# logic.net
KiCad netlist of a schematic drawn in EAGLE
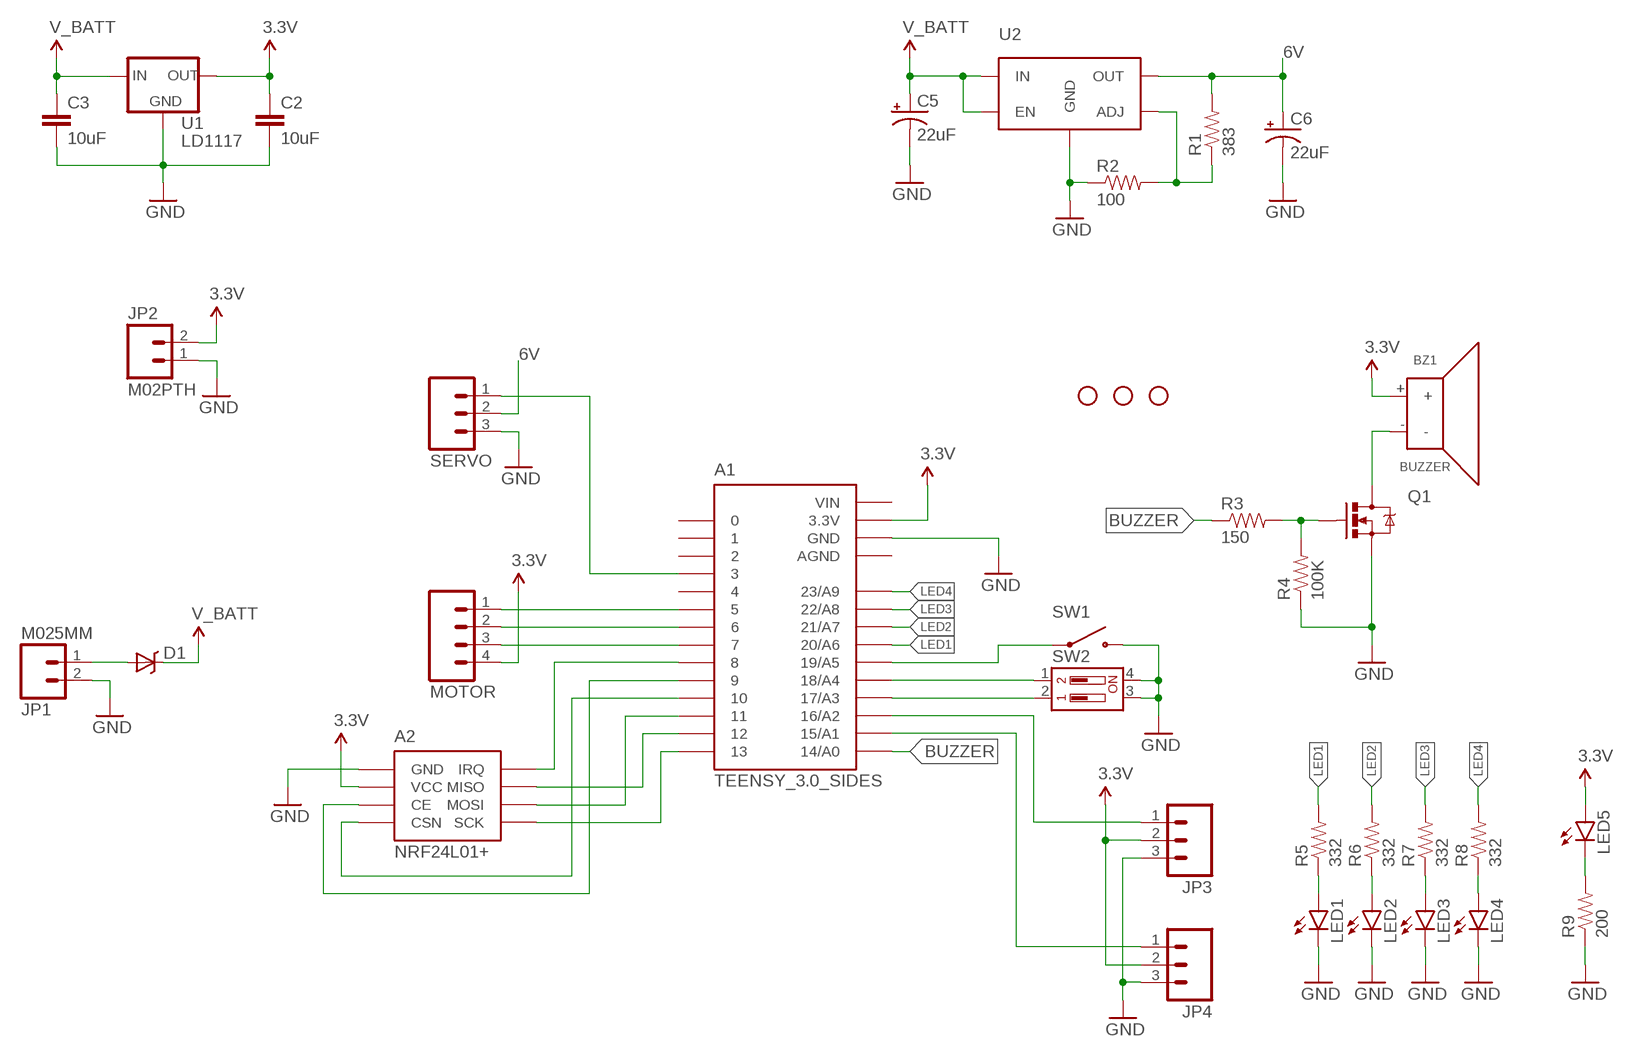
[diagram p0: schematic, sheet 1]

(export (version "E")
  (design (tool "Eeschema 10.0.6"))
  (components
    (comp (ref "A1")
      (value "TEENSY_3.0_SIDES")
      (footprint "eagle-import:TEENSY_3.0_SIDES")
      (libsource (lib "eagle-import") (part "TEENSY_3.0_SIDES"))
    )
    (comp (ref "A2")
      (value "NRF24L01+")
      (footprint "eagle-import:NRF24L01+")
      (libsource (lib "eagle-import") (part "NRF24L01+"))
    )
    (comp (ref "BZ1")
      (value "BUZZER")
      (footprint "eagle-import:BUZZER")
      (libsource (lib "eagle-import") (part "BUZZER"))
    )
    (comp (ref "C2")
      (value "10uF")
      (footprint "eagle-import:1206")
      (libsource (lib "eagle-import") (part "CAP1206"))
    )
    (comp (ref "C3")
      (value "10uF")
      (footprint "eagle-import:1206")
      (libsource (lib "eagle-import") (part "CAP1206"))
    )
    (comp (ref "C5")
      (value "22uF")
      (footprint "eagle-import:CPOL-RADIAL-10UF-25V")
      (libsource (lib "eagle-import") (part "CAP_POLPTH2"))
    )
    (comp (ref "C6")
      (value "22uF")
      (footprint "eagle-import:CPOL-RADIAL-10UF-25V")
      (libsource (lib "eagle-import") (part "CAP_POLPTH2"))
    )
    (comp (ref "D1")
      (value "DIODE-SCHOTTKY_")
      (footprint "eagle-import:SMA-DIODE")
      (libsource (lib "eagle-import") (part "DIODE-SCHOTTKY_"))
    )
    (comp (ref "JP1")
      (value "M025MM")
      (footprint "eagle-import:SCREWTERMINAL-5MM-2")
      (libsource (lib "eagle-import") (part "M025MM"))
    )
    (comp (ref "JP2")
      (value "M02PTH")
      (footprint "eagle-import:1X02")
      (libsource (lib "eagle-import") (part "M02PTH"))
    )
    (comp (ref "JP3")
      (value "M03LOCK")
      (footprint "eagle-import:1X03_LOCK")
      (libsource (lib "eagle-import") (part "M03LOCK"))
    )
    (comp (ref "JP4")
      (value "M03LOCK")
      (footprint "eagle-import:1X03_LOCK")
      (libsource (lib "eagle-import") (part "M03LOCK"))
    )
    (comp (ref "LED1")
      (value "LED0603")
      (footprint "eagle-import:LED-0603")
      (libsource (lib "eagle-import") (part "LED0603"))
    )
    (comp (ref "LED2")
      (value "LED0603")
      (footprint "eagle-import:LED-0603")
      (libsource (lib "eagle-import") (part "LED0603"))
    )
    (comp (ref "LED3")
      (value "LED0603")
      (footprint "eagle-import:LED-0603")
      (libsource (lib "eagle-import") (part "LED0603"))
    )
    (comp (ref "LED4")
      (value "LED0603")
      (footprint "eagle-import:LED-0603")
      (libsource (lib "eagle-import") (part "LED0603"))
    )
    (comp (ref "LED5")
      (value "LED0603")
      (footprint "eagle-import:LED-0603")
      (libsource (lib "eagle-import") (part "LED0603"))
    )
    (comp (ref "MOTOR")
      (value "M04LOCK")
      (footprint "eagle-import:1X04_LOCK")
      (libsource (lib "eagle-import") (part "M04LOCK"))
    )
    (comp (ref "Q1")
      (value "MOSFET-NCHANNELBSS123LT1G")
      (footprint "eagle-import:SOT23-3")
      (libsource (lib "eagle-import") (part "MOSFET-NCHANNELBSS123LT1G"))
    )
    (comp (ref "R1")
      (value "383")
      (footprint "eagle-import:0603-RES")
      (libsource (lib "eagle-import") (part "RESISTOR0603-RES"))
    )
    (comp (ref "R2")
      (value "100")
      (footprint "eagle-import:0603-RES")
      (libsource (lib "eagle-import") (part "RESISTOR0603-RES"))
    )
    (comp (ref "R3")
      (value "150")
      (footprint "eagle-import:0603-RES")
      (libsource (lib "eagle-import") (part "RESISTOR0603-RES"))
    )
    (comp (ref "R4")
      (value "100K")
      (footprint "eagle-import:0603-RES")
      (libsource (lib "eagle-import") (part "RESISTOR0603-RES"))
    )
    (comp (ref "R5")
      (value "332")
      (footprint "eagle-import:0603-RES")
      (libsource (lib "eagle-import") (part "RESISTOR0603-RES"))
    )
    (comp (ref "R6")
      (value "332")
      (footprint "eagle-import:0603-RES")
      (libsource (lib "eagle-import") (part "RESISTOR0603-RES"))
    )
    (comp (ref "R7")
      (value "332")
      (footprint "eagle-import:0603-RES")
      (libsource (lib "eagle-import") (part "RESISTOR0603-RES"))
    )
    (comp (ref "R8")
      (value "332")
      (footprint "eagle-import:0603-RES")
      (libsource (lib "eagle-import") (part "RESISTOR0603-RES"))
    )
    (comp (ref "R9")
      (value "200")
      (footprint "eagle-import:0603-RES")
      (libsource (lib "eagle-import") (part "RESISTOR0603-RES"))
    )
    (comp (ref "SERVO")
      (value "M03LOCK_LONGPADS")
      (footprint "eagle-import:1X03_LOCK_LONGPADS")
      (libsource (lib "eagle-import") (part "M03LOCK_LONGPADS"))
    )
    (comp (ref "STANDOFF1")
      (value "STAND-OFF")
      (footprint "eagle-import:STAND-OFF")
      (libsource (lib "eagle-import") (part "STAND-OFF"))
    )
    (comp (ref "STANDOFF2")
      (value "STAND-OFF")
      (footprint "eagle-import:STAND-OFF")
      (libsource (lib "eagle-import") (part "STAND-OFF"))
    )
    (comp (ref "STANDOFF3")
      (value "STAND-OFF")
      (footprint "eagle-import:STAND-OFF")
      (libsource (lib "eagle-import") (part "STAND-OFF"))
    )
    (comp (ref "SW1")
      (value "FSM4JSMA")
      (footprint "eagle-import:FSM4JSMA")
      (libsource (lib "eagle-import") (part "FSM4JSMA"))
    )
    (comp (ref "SW2")
      (value "2-POS-DIPCTS-THRU-HOLE")
      (footprint "eagle-import:209-2LPST")
      (libsource (lib "eagle-import") (part "2-POS-DIPCTS-THRU-HOLE"))
    )
    (comp (ref "U1")
      (value "LD1117")
      (footprint "eagle-import:SOT-223")
      (libsource (lib "eagle-import") (part "LD1117"))
    )
    (comp (ref "U2")
      (value "MIC29302AWD")
      (footprint "eagle-import:TO-252-5")
      (libsource (lib "eagle-import") (part "MIC29302AWD"))
    )
  )
  (nets
    (net (code "1") (name "/6V") (class "Default")
      (node (ref "C6") (pin "1") (pinfunction "+_1") (pintype "passive"))
      (node (ref "R1") (pin "2") (pinfunction "2_2") (pintype "passive"))
      (node (ref "SERVO") (pin "2") (pinfunction "2_2") (pintype "passive"))
      (node (ref "U2") (pin "P$4") (pinfunction "OUT_P$4") (pintype "bidirectional"))
    )
    (net (code "2") (name "/AGND") (class "Default")
      (node (ref "A1") (pin "AGND") (pinfunction "AGND_AGND") (pintype "power_in"))
    )
    (net (code "3") (name "/VIN") (class "Default")
      (node (ref "A1") (pin "VIN") (pinfunction "VIN_VIN") (pintype "power_in"))
    )
    (net (code "4") (name "3.3V") (class "Default")
      (node (ref "A1") (pin "3.3V") (pinfunction "3.3V_3.3V") (pintype "power_in"))
      (node (ref "A2") (pin "2") (pinfunction "VCC_2") (pintype "bidirectional"))
      (node (ref "BZ1") (pin "+") (pinfunction "+_+") (pintype "bidirectional"))
      (node (ref "C2") (pin "1") (pinfunction "1_1") (pintype "passive"))
      (node (ref "JP2") (pin "2") (pinfunction "2_2") (pintype "passive"))
      (node (ref "JP3") (pin "2") (pinfunction "2_2") (pintype "passive"))
      (node (ref "JP4") (pin "2") (pinfunction "2_2") (pintype "passive"))
      (node (ref "LED5") (pin "A") (pinfunction "A_A") (pintype "passive"))
      (node (ref "MOTOR") (pin "4") (pinfunction "4_4") (pintype "passive"))
      (node (ref "U1") (pin "2") (pinfunction "OUT_2") (pintype "passive"))
      (node (ref "U1") (pin "4") (pinfunction "OUT_4") (pintype "passive"))
    )
    (net (code "5") (name "BUZZER") (class "Default")
      (node (ref "A1") (pin "14/A0") (pinfunction "14/A0_14/A0") (pintype "bidirectional"))
      (node (ref "R3") (pin "1") (pinfunction "1_1") (pintype "passive"))
    )
    (net (code "6") (name "GND") (class "Default")
      (node (ref "A1") (pin "GND") (pinfunction "GND_GND") (pintype "power_in"))
      (node (ref "A2") (pin "1") (pinfunction "GND_1") (pintype "bidirectional"))
      (node (ref "C2") (pin "2") (pinfunction "2_2") (pintype "passive"))
      (node (ref "C3") (pin "2") (pinfunction "2_2") (pintype "passive"))
      (node (ref "C5") (pin "2") (pinfunction "-_2") (pintype "passive"))
      (node (ref "C6") (pin "2") (pinfunction "-_2") (pintype "passive"))
      (node (ref "JP1") (pin "2") (pinfunction "2_2") (pintype "passive"))
      (node (ref "JP2") (pin "1") (pinfunction "1_1") (pintype "passive"))
      (node (ref "JP3") (pin "3") (pinfunction "3_3") (pintype "passive"))
      (node (ref "JP4") (pin "3") (pinfunction "3_3") (pintype "passive"))
      (node (ref "LED1") (pin "C") (pinfunction "C_C") (pintype "passive"))
      (node (ref "LED2") (pin "C") (pinfunction "C_C") (pintype "passive"))
      (node (ref "LED3") (pin "C") (pinfunction "C_C") (pintype "passive"))
      (node (ref "LED4") (pin "C") (pinfunction "C_C") (pintype "passive"))
      (node (ref "Q1") (pin "2") (pinfunction "S_2") (pintype "passive"))
      (node (ref "R2") (pin "1") (pinfunction "1_1") (pintype "passive"))
      (node (ref "R4") (pin "1") (pinfunction "1_1") (pintype "passive"))
      (node (ref "R9") (pin "1") (pinfunction "1_1") (pintype "passive"))
      (node (ref "SERVO") (pin "3") (pinfunction "3_3") (pintype "passive"))
      (node (ref "SW1") (pin "3") (pinfunction "2_3") (pintype "bidirectional"))
      (node (ref "SW1") (pin "4") (pinfunction "2_4") (pintype "bidirectional"))
      (node (ref "SW2") (pin "3") (pinfunction "P$3_3") (pintype "bidirectional"))
      (node (ref "SW2") (pin "4") (pinfunction "P$4_4") (pintype "bidirectional"))
      (node (ref "U1") (pin "1") (pinfunction "GND_1") (pintype "input"))
      (node (ref "U2") (pin "P$3") (pinfunction "GND_P$3") (pintype "bidirectional"))
      (node (ref "U2") (pin "PAD") (pinfunction "GND_PAD") (pintype "bidirectional"))
    )
    (net (code "7") (name "LED1") (class "Default")
      (node (ref "A1") (pin "20/A6") (pinfunction "20/A6_20/A6") (pintype "bidirectional"))
      (node (ref "R5") (pin "2") (pinfunction "2_2") (pintype "passive"))
    )
    (net (code "8") (name "LED2") (class "Default")
      (node (ref "A1") (pin "21/A7") (pinfunction "21/A7_21/A7") (pintype "bidirectional"))
      (node (ref "R6") (pin "2") (pinfunction "2_2") (pintype "passive"))
    )
    (net (code "9") (name "LED3") (class "Default")
      (node (ref "A1") (pin "22/A8") (pinfunction "22/A8_22/A8") (pintype "bidirectional"))
      (node (ref "R7") (pin "2") (pinfunction "2_2") (pintype "passive"))
    )
    (net (code "10") (name "LED4") (class "Default")
      (node (ref "A1") (pin "23/A9") (pinfunction "23/A9_23/A9") (pintype "bidirectional"))
      (node (ref "R8") (pin "2") (pinfunction "2_2") (pintype "passive"))
    )
    (net (code "11") (name "Net-(A1-Pad3)") (class "Default")
      (node (ref "A1") (pin "3") (pinfunction "3_3") (pintype "bidirectional"))
      (node (ref "SERVO") (pin "1") (pinfunction "1_1") (pintype "passive"))
    )
    (net (code "12") (name "Net-(A1-Pad5)") (class "Default")
      (node (ref "A1") (pin "5") (pinfunction "5_5") (pintype "bidirectional"))
      (node (ref "MOTOR") (pin "1") (pinfunction "1_1") (pintype "passive"))
    )
    (net (code "13") (name "Net-(A1-Pad6)") (class "Default")
      (node (ref "A1") (pin "6") (pinfunction "6_6") (pintype "bidirectional"))
      (node (ref "MOTOR") (pin "2") (pinfunction "2_2") (pintype "passive"))
    )
    (net (code "14") (name "Net-(A1-Pad7)") (class "Default")
      (node (ref "A1") (pin "7") (pinfunction "7_7") (pintype "bidirectional"))
      (node (ref "MOTOR") (pin "3") (pinfunction "3_3") (pintype "passive"))
    )
    (net (code "15") (name "Net-(A1-Pad15{slash}A1)") (class "Default")
      (node (ref "A1") (pin "15/A1") (pinfunction "15/A1_15/A1") (pintype "bidirectional"))
      (node (ref "JP4") (pin "1") (pinfunction "1_1") (pintype "passive"))
    )
    (net (code "16") (name "Net-(A1-Pad16{slash}A2)") (class "Default")
      (node (ref "A1") (pin "16/A2") (pinfunction "16/A2_16/A2") (pintype "bidirectional"))
      (node (ref "JP3") (pin "1") (pinfunction "1_1") (pintype "passive"))
    )
    (net (code "17") (name "Net-(A1-Pad19{slash}A5)") (class "Default")
      (node (ref "A1") (pin "19/A5") (pinfunction "19/A5_19/A5") (pintype "bidirectional"))
      (node (ref "SW1") (pin "1") (pinfunction "1_1") (pintype "bidirectional"))
      (node (ref "SW1") (pin "2") (pinfunction "1_2") (pintype "bidirectional"))
    )
    (net (code "18") (name "Net-(A2-CE)") (class "Default")
      (node (ref "A1") (pin "9") (pinfunction "9_9") (pintype "bidirectional"))
      (node (ref "A2") (pin "3") (pinfunction "CE_3") (pintype "bidirectional"))
    )
    (net (code "19") (name "Net-(A2-CSN)") (class "Default")
      (node (ref "A1") (pin "10") (pinfunction "10_10") (pintype "bidirectional"))
      (node (ref "A2") (pin "4") (pinfunction "CSN_4") (pintype "bidirectional"))
    )
    (net (code "20") (name "Net-(A2-IRQ)") (class "Default")
      (node (ref "A1") (pin "8") (pinfunction "8_8") (pintype "bidirectional"))
      (node (ref "A2") (pin "8") (pinfunction "IRQ_8") (pintype "bidirectional"))
    )
    (net (code "21") (name "Net-(A2-MISO)") (class "Default")
      (node (ref "A1") (pin "12") (pinfunction "12_12") (pintype "bidirectional"))
      (node (ref "A2") (pin "7") (pinfunction "MISO_7") (pintype "bidirectional"))
    )
    (net (code "22") (name "Net-(A2-MOSI)") (class "Default")
      (node (ref "A1") (pin "11") (pinfunction "11_11") (pintype "bidirectional"))
      (node (ref "A2") (pin "6") (pinfunction "MOSI_6") (pintype "bidirectional"))
    )
    (net (code "23") (name "Net-(A2-SCK)") (class "Default")
      (node (ref "A1") (pin "13") (pinfunction "13_13") (pintype "bidirectional"))
      (node (ref "A2") (pin "5") (pinfunction "SCK_5") (pintype "bidirectional"))
    )
    (net (code "24") (name "Net-(D1-PadA)") (class "Default")
      (node (ref "D1") (pin "A") (pinfunction "A_A") (pintype "passive"))
      (node (ref "JP1") (pin "1") (pinfunction "1_1") (pintype "passive"))
    )
    (net (code "25") (name "Net-(LED1-PadA)") (class "Default")
      (node (ref "LED1") (pin "A") (pinfunction "A_A") (pintype "passive"))
      (node (ref "R5") (pin "1") (pinfunction "1_1") (pintype "passive"))
    )
    (net (code "26") (name "Net-(LED2-PadA)") (class "Default")
      (node (ref "LED2") (pin "A") (pinfunction "A_A") (pintype "passive"))
      (node (ref "R6") (pin "1") (pinfunction "1_1") (pintype "passive"))
    )
    (net (code "27") (name "Net-(LED3-PadA)") (class "Default")
      (node (ref "LED3") (pin "A") (pinfunction "A_A") (pintype "passive"))
      (node (ref "R7") (pin "1") (pinfunction "1_1") (pintype "passive"))
    )
    (net (code "28") (name "Net-(LED4-PadA)") (class "Default")
      (node (ref "LED4") (pin "A") (pinfunction "A_A") (pintype "passive"))
      (node (ref "R8") (pin "1") (pinfunction "1_1") (pintype "passive"))
    )
    (net (code "29") (name "Net-(LED5-PadC)") (class "Default")
      (node (ref "LED5") (pin "C") (pinfunction "C_C") (pintype "passive"))
      (node (ref "R9") (pin "2") (pinfunction "2_2") (pintype "passive"))
    )
    (net (code "30") (name "Net-(Q1-D)") (class "Default")
      (node (ref "BZ1") (pin "-") (pinfunction "-_-") (pintype "bidirectional"))
      (node (ref "Q1") (pin "3") (pinfunction "D_3") (pintype "passive"))
    )
    (net (code "31") (name "Net-(Q1-G)") (class "Default")
      (node (ref "Q1") (pin "1") (pinfunction "G_1") (pintype "passive"))
      (node (ref "R3") (pin "2") (pinfunction "2_2") (pintype "passive"))
      (node (ref "R4") (pin "2") (pinfunction "2_2") (pintype "passive"))
    )
    (net (code "32") (name "Net-(SW2-P$1)") (class "Default")
      (node (ref "A1") (pin "18/A4") (pinfunction "18/A4_18/A4") (pintype "bidirectional"))
      (node (ref "SW2") (pin "1") (pinfunction "P$1_1") (pintype "bidirectional"))
    )
    (net (code "33") (name "Net-(SW2-P$2)") (class "Default")
      (node (ref "A1") (pin "17/A3") (pinfunction "17/A3_17/A3") (pintype "bidirectional"))
      (node (ref "SW2") (pin "2") (pinfunction "P$2_2") (pintype "bidirectional"))
    )
    (net (code "34") (name "Net-(U2-ADJ)") (class "Default")
      (node (ref "R1") (pin "1") (pinfunction "1_1") (pintype "passive"))
      (node (ref "R2") (pin "2") (pinfunction "2_2") (pintype "passive"))
      (node (ref "U2") (pin "P$5") (pinfunction "ADJ_P$5") (pintype "bidirectional"))
    )
    (net (code "35") (name "V_BATT") (class "Default")
      (node (ref "C3") (pin "1") (pinfunction "1_1") (pintype "passive"))
      (node (ref "C5") (pin "1") (pinfunction "+_1") (pintype "passive"))
      (node (ref "D1") (pin "C") (pinfunction "C_C") (pintype "passive"))
      (node (ref "U1") (pin "3") (pinfunction "IN_3") (pintype "input"))
      (node (ref "U2") (pin "P$1") (pinfunction "EN_P$1") (pintype "bidirectional"))
      (node (ref "U2") (pin "P$2") (pinfunction "IN_P$2") (pintype "bidirectional"))
    )
    (net (code "36") (name "unconnected-(A1-Pad0)") (class "Default")
      (node (ref "A1") (pin "0") (pinfunction "0_0") (pintype "bidirectional"))
    )
    (net (code "37") (name "unconnected-(A1-Pad1)") (class "Default")
      (node (ref "A1") (pin "1") (pinfunction "1_1") (pintype "bidirectional"))
    )
    (net (code "38") (name "unconnected-(A1-Pad2)") (class "Default")
      (node (ref "A1") (pin "2") (pinfunction "2_2") (pintype "bidirectional"))
    )
    (net (code "39") (name "unconnected-(A1-Pad4)") (class "Default")
      (node (ref "A1") (pin "4") (pinfunction "4_4") (pintype "bidirectional"))
    )
  )
)
